# Interfaces.net
KiCad netlist of a schematic drawn in Altium Designer
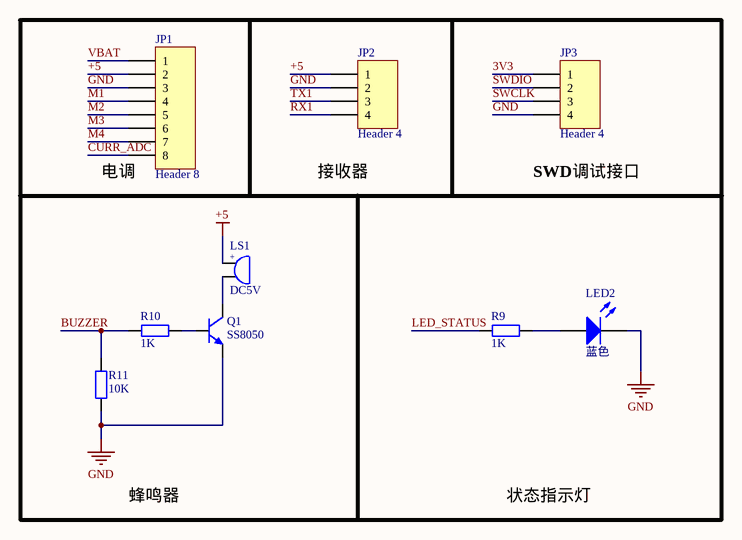
[diagram p0: Interfaces.SchDoc]

(export (version "E")
  (design (tool "Eeschema 10.0.6"))
  (components
    (comp (ref "JP1")
      (value "Header 8")
      (footprint "SH1.0-WT-8P")
      (description "Header, 8-Pin")
      (fields (field (name "PUBLISHER") "Altium Limited"))
      (libsource (lib "ST Miscellaneous Connectors") (part "Header 8"))
    )
    (comp (ref "JP2")
      (value "Header 4")
      (footprint "PAD-1X4-SMD")
      (description "Header, 4-Pin")
      (fields (field (name "PUBLISHER") "Altium Limited"))
      (libsource (lib "ST Miscellaneous Connectors") (part "Header 4"))
    )
    (comp (ref "JP3")
      (value "Header 4")
      (footprint "PAD-1X4-SMD")
      (description "Header, 4-Pin")
      (fields (field (name "PUBLISHER") "Altium Limited"))
      (libsource (lib "ST Miscellaneous Connectors") (part "Header 4"))
    )
    (comp (ref "LED2")
      (value "蓝色")
      (footprint "LED0603_B")
      (description "贴片LED")
      (libsource (lib "0.3 - LED发光二极管-IR二极管_接收管-光耦") (part "LED"))
    )
    (comp (ref "LS1")
      (value "DC5V")
      (footprint "BUZZER")
      (description "蜂鸣器")
      (libsource (lib "0.5 - 按键_开关_蜂鸣器_电池_测试点_Mark点_铜柱") (part "BEEP"))
    )
    (comp (ref "Q1")
      (value "SS8050")
      (footprint "SOT23-3L")
      (description "高频放大-NPN型")
      (libsource (lib "0.4 - 三极管-场效应管-可控硅") (part "8050-SMD"))
    )
    (comp (ref "R9")
      (value "1K")
      (footprint "R0402_M")
      (description "贴片电阻")
      (libsource (lib "0.1 - 电阻-电容-电感-保险丝-晶振-晶体-磁珠-电位器-法拉电容-馈通电容") (part "R"))
    )
    (comp (ref "R10")
      (value "1K")
      (footprint "R0402_M")
      (description "贴片电阻")
      (libsource (lib "0.1 - 电阻-电容-电感-保险丝-晶振-晶体-磁珠-电位器-法拉电容-馈通电容") (part "R"))
    )
    (comp (ref "R11")
      (value "10K")
      (footprint "R0402_M")
      (description "贴片电阻")
      (libsource (lib "0.1 - 电阻-电容-电感-保险丝-晶振-晶体-磁珠-电位器-法拉电容-馈通电容") (part "R"))
    )
  )
  (nets
    (net (code "1") (name "+5") (class "Default")
      (node (ref "JP1") (pin "2") (pinfunction "2_2") (pintype "passive"))
      (node (ref "JP2") (pin "1") (pinfunction "1_1") (pintype "passive"))
      (node (ref "LS1") (pin "1") (pinfunction "1_1") (pintype "passive"))
    )
    (net (code "2") (name "/3V3") (class "Default")
      (node (ref "JP3") (pin "1") (pinfunction "1_1") (pintype "passive"))
    )
    (net (code "3") (name "/BUZZER") (class "Default")
      (node (ref "R10") (pin "1") (pinfunction "1_1") (pintype "passive"))
      (node (ref "R11") (pin "2") (pinfunction "2_2") (pintype "passive"))
    )
    (net (code "4") (name "/CURR_ADC") (class "Default")
      (node (ref "JP1") (pin "8") (pinfunction "8_8") (pintype "passive"))
    )
    (net (code "5") (name "/LED_STATUS") (class "Default")
      (node (ref "R9") (pin "1") (pinfunction "1_1") (pintype "passive"))
    )
    (net (code "6") (name "/M1") (class "Default")
      (node (ref "JP1") (pin "4") (pinfunction "4_4") (pintype "passive"))
    )
    (net (code "7") (name "/M2") (class "Default")
      (node (ref "JP1") (pin "5") (pinfunction "5_5") (pintype "passive"))
    )
    (net (code "8") (name "/M3") (class "Default")
      (node (ref "JP1") (pin "6") (pinfunction "6_6") (pintype "passive"))
    )
    (net (code "9") (name "/M4") (class "Default")
      (node (ref "JP1") (pin "7") (pinfunction "7_7") (pintype "passive"))
    )
    (net (code "10") (name "/RX1") (class "Default")
      (node (ref "JP2") (pin "4") (pinfunction "4_4") (pintype "passive"))
    )
    (net (code "11") (name "/SWCLK") (class "Default")
      (node (ref "JP3") (pin "3") (pinfunction "3_3") (pintype "passive"))
    )
    (net (code "12") (name "/SWDIO") (class "Default")
      (node (ref "JP3") (pin "2") (pinfunction "2_2") (pintype "passive"))
    )
    (net (code "13") (name "/TX1") (class "Default")
      (node (ref "JP2") (pin "3") (pinfunction "3_3") (pintype "passive"))
    )
    (net (code "14") (name "/VBAT") (class "Default")
      (node (ref "JP1") (pin "1") (pinfunction "1_1") (pintype "passive"))
    )
    (net (code "15") (name "GND") (class "Default")
      (node (ref "JP1") (pin "3") (pinfunction "3_3") (pintype "passive"))
      (node (ref "JP2") (pin "2") (pinfunction "2_2") (pintype "passive"))
      (node (ref "JP3") (pin "4") (pinfunction "4_4") (pintype "passive"))
      (node (ref "LED2") (pin "2") (pinfunction "K_2") (pintype "passive"))
      (node (ref "Q1") (pin "2") (pinfunction "E_2") (pintype "passive"))
      (node (ref "R11") (pin "1") (pinfunction "1_1") (pintype "passive"))
    )
    (net (code "16") (name "Net-(LED2-A)") (class "Default")
      (node (ref "LED2") (pin "1") (pinfunction "A_1") (pintype "passive"))
      (node (ref "R9") (pin "2") (pinfunction "2_2") (pintype "passive"))
    )
    (net (code "17") (name "Net-(Q1-B)") (class "Default")
      (node (ref "Q1") (pin "1") (pinfunction "B_1") (pintype "passive"))
      (node (ref "R10") (pin "2") (pinfunction "2_2") (pintype "passive"))
    )
    (net (code "18") (name "Net-(Q1-C)") (class "Default")
      (node (ref "LS1") (pin "2") (pinfunction "2_2") (pintype "passive"))
      (node (ref "Q1") (pin "3") (pinfunction "C_3") (pintype "passive"))
    )
  )
)
